# POV_02.net
KiCad netlist of a schematic drawn in EAGLE
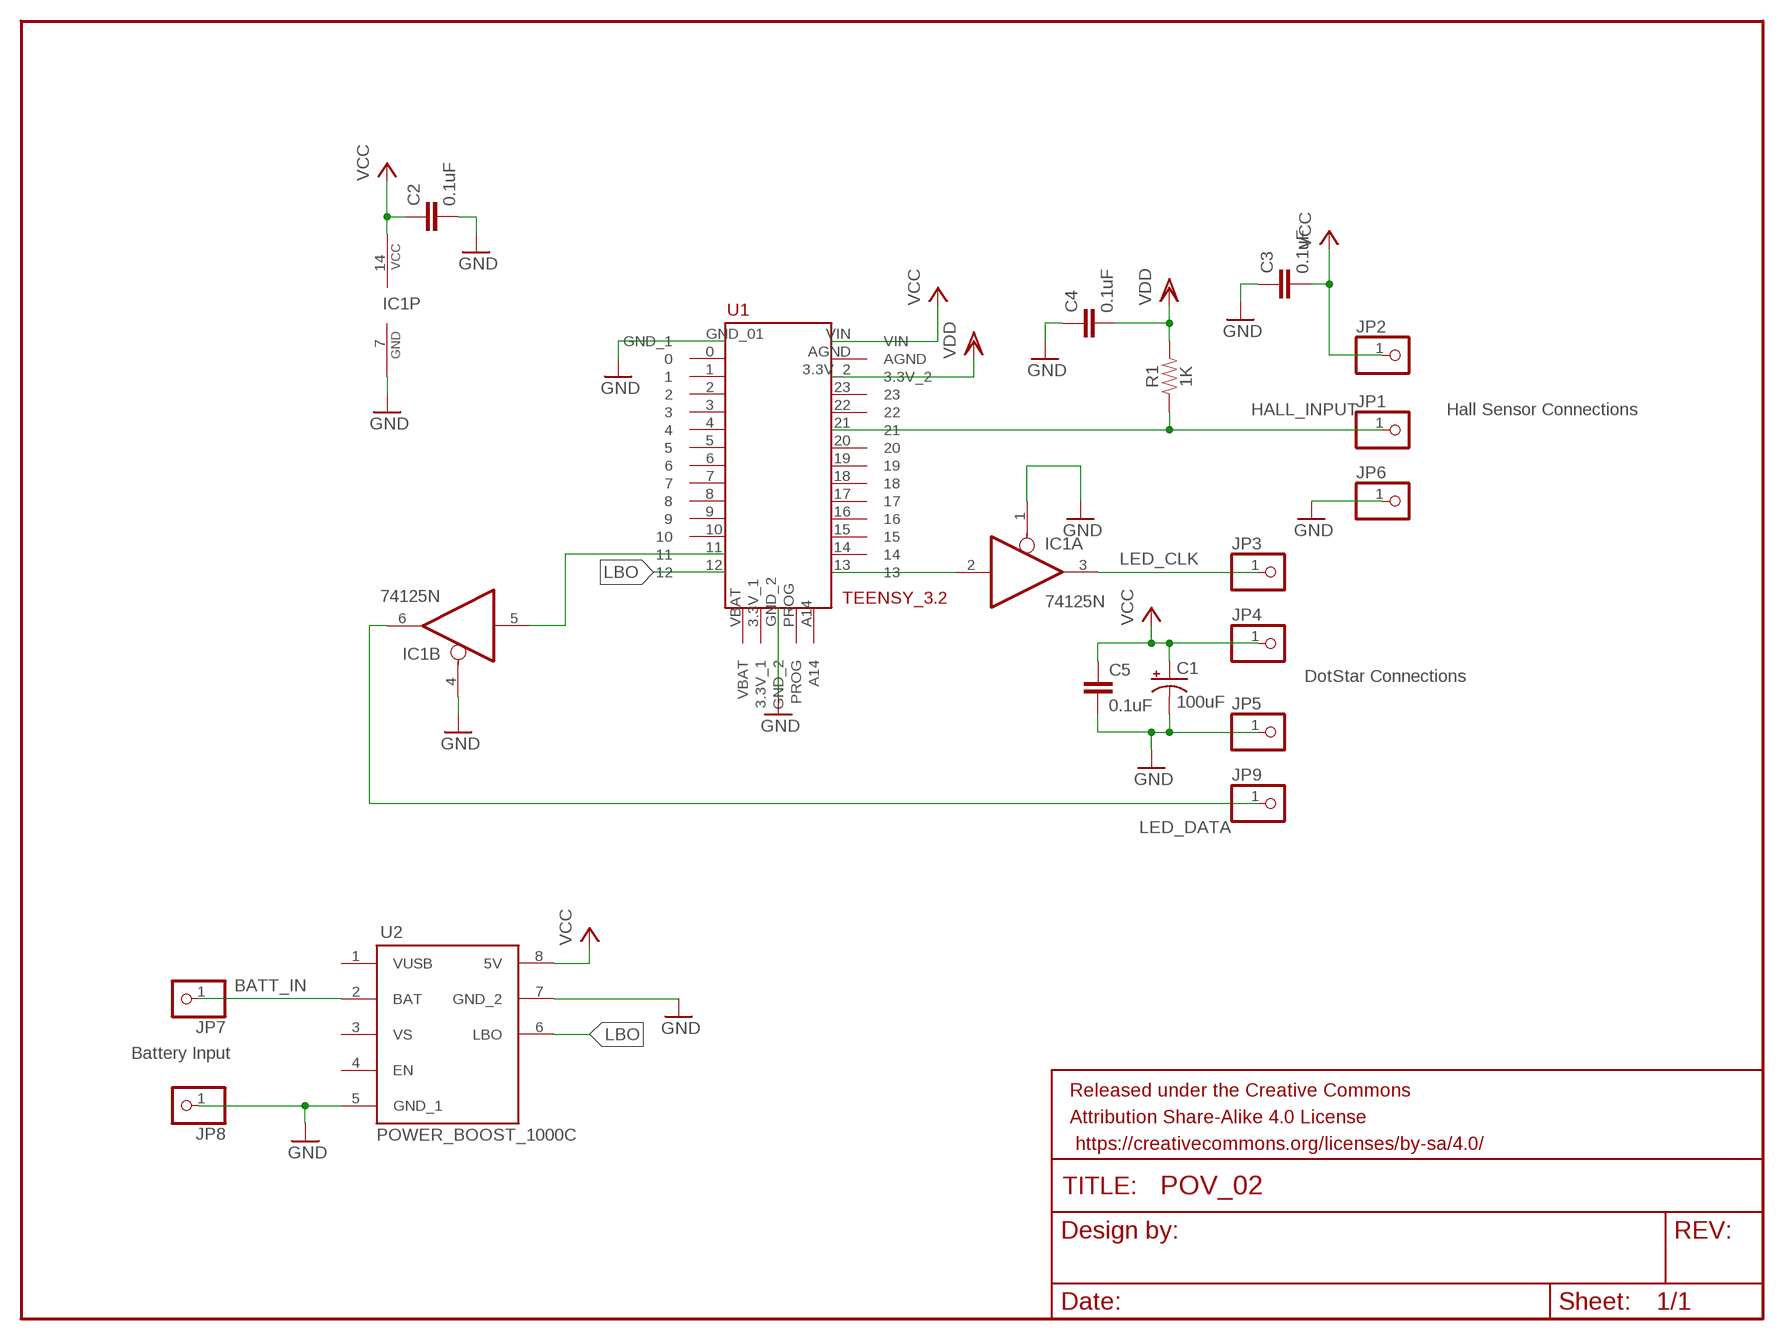
[diagram p0: schematic, sheet 1]

(export (version "E")
  (design (tool "Eeschema 10.0.6"))
  (components
    (comp (ref "C1")
      (value "100uF")
      (footprint "eagle-import:CPOL-RADIAL-2.5MM-6.5MM")
      (libsource (lib "eagle-import") (part "100UF-POLAR-RADIAL-2.5MM-25V-20%"))
    )
    (comp (ref "C2")
      (value "0.1uF")
      (footprint "eagle-import:CAP-PTH-SMALL-KIT")
      (libsource (lib "eagle-import") (part "0.1UF-KIT-EZ-50V-20%"))
    )
    (comp (ref "C3")
      (value "0.1uF")
      (footprint "eagle-import:CAP-PTH-SMALL-KIT")
      (libsource (lib "eagle-import") (part "0.1UF-KIT-EZ-50V-20%"))
    )
    (comp (ref "C4")
      (value "0.1uF")
      (footprint "eagle-import:CAP-PTH-SMALL-KIT")
      (libsource (lib "eagle-import") (part "0.1UF-KIT-EZ-50V-20%"))
    )
    (comp (ref "C5")
      (value "0.1uF")
      (footprint "eagle-import:CAP-PTH-SMALL-KIT")
      (libsource (lib "eagle-import") (part "0.1UF-KIT-EZ-50V-20%"))
    )
    (comp (ref "FRAME1")
      (value "FRAME-LETTERNO_PACKAGE")
      (footprint "eagle-import:DUMMY")
      (fields (field (name "DESIGNER") "Nobody"))
      (libsource (lib "eagle-import") (part "FRAME-LETTERNO_PACKAGE"))
    )
    (comp (ref "IC1")
      (value "74125N")
      (footprint "eagle-import:DIL14")
      (libsource (lib "eagle-import") (part "74125N"))
    )
    (comp (ref "JP1")
      (value "HEADER-1X1ROUND")
      (footprint "eagle-import:1X01_ROUND")
      (libsource (lib "eagle-import") (part "HEADER-1X1ROUND"))
    )
    (comp (ref "JP2")
      (value "HEADER-1X1ROUND")
      (footprint "eagle-import:1X01_ROUND")
      (libsource (lib "eagle-import") (part "HEADER-1X1ROUND"))
    )
    (comp (ref "JP3")
      (value "HEADER-1X1ROUND")
      (footprint "eagle-import:1X01_ROUND")
      (libsource (lib "eagle-import") (part "HEADER-1X1ROUND"))
    )
    (comp (ref "JP4")
      (value "HEADER-1X1ROUND")
      (footprint "eagle-import:1X01_ROUND")
      (libsource (lib "eagle-import") (part "HEADER-1X1ROUND"))
    )
    (comp (ref "JP5")
      (value "HEADER-1X1ROUND")
      (footprint "eagle-import:1X01_ROUND")
      (libsource (lib "eagle-import") (part "HEADER-1X1ROUND"))
    )
    (comp (ref "JP6")
      (value "HEADER-1X1ROUND")
      (footprint "eagle-import:1X01_ROUND")
      (libsource (lib "eagle-import") (part "HEADER-1X1ROUND"))
    )
    (comp (ref "JP7")
      (value "HEADER-1X1ROUND")
      (footprint "eagle-import:1X01_ROUND")
      (libsource (lib "eagle-import") (part "HEADER-1X1ROUND"))
    )
    (comp (ref "JP8")
      (value "HEADER-1X1ROUND")
      (footprint "eagle-import:1X01_ROUND")
      (libsource (lib "eagle-import") (part "HEADER-1X1ROUND"))
    )
    (comp (ref "JP9")
      (value "HEADER-1X1ROUND")
      (footprint "eagle-import:1X01_ROUND")
      (libsource (lib "eagle-import") (part "HEADER-1X1ROUND"))
    )
    (comp (ref "R1")
      (value "1K")
      (footprint "eagle-import:AXIAL-0.3")
      (libsource (lib "eagle-import") (part "RESISTORAXIAL-0.3"))
    )
    (comp (ref "U1")
      (value "TEENSY_3.2")
      (footprint "eagle-import:TEENSEY_3.2")
      (libsource (lib "eagle-import") (part "TEENSY_3.2"))
    )
    (comp (ref "U2")
      (value "POWER_BOOST_1000C")
      (footprint "eagle-import:POWER_BOOST_1000C")
      (libsource (lib "eagle-import") (part "POWER_BOOST_1000C"))
    )
  )
  (nets
    (net (code "1") (name "/BATT_IN") (class "Default")
      (node (ref "JP7") (pin "1") (pinfunction "1_1") (pintype "passive"))
      (node (ref "U2") (pin "2") (pinfunction "BAT_2") (pintype "bidirectional"))
    )
    (net (code "2") (name "/HALL_INPUT") (class "Default")
      (node (ref "JP1") (pin "1") (pinfunction "1_1") (pintype "passive"))
      (node (ref "R1") (pin "P$1") (pinfunction "1_P$1") (pintype "passive"))
      (node (ref "U1") (pin "21") (pinfunction "21_21") (pintype "bidirectional"))
    )
    (net (code "3") (name "/LED_CLK") (class "Default")
      (node (ref "IC1") (pin "3") (pinfunction "O_3") (pintype "tri_state"))
      (node (ref "JP3") (pin "1") (pinfunction "1_1") (pintype "passive"))
    )
    (net (code "4") (name "/LED_DATA") (class "Default")
      (node (ref "IC1") (pin "6") (pinfunction "O_6") (pintype "tri_state"))
      (node (ref "JP9") (pin "1") (pinfunction "1_1") (pintype "passive"))
    )
    (net (code "5") (name "GND") (class "Default")
      (node (ref "C1") (pin "2") (pinfunction "-_2") (pintype "passive"))
      (node (ref "C2") (pin "2") (pinfunction "2_2") (pintype "passive"))
      (node (ref "C3") (pin "1") (pinfunction "1_1") (pintype "passive"))
      (node (ref "C4") (pin "1") (pinfunction "1_1") (pintype "passive"))
      (node (ref "C5") (pin "2") (pinfunction "2_2") (pintype "passive"))
      (node (ref "IC1") (pin "1") (pinfunction "OE_1") (pintype "input"))
      (node (ref "IC1") (pin "4") (pinfunction "OE_4") (pintype "input"))
      (node (ref "IC1") (pin "7") (pinfunction "GND_7") (pintype "power_in"))
      (node (ref "JP5") (pin "1") (pinfunction "1_1") (pintype "passive"))
      (node (ref "JP6") (pin "1") (pinfunction "1_1") (pintype "passive"))
      (node (ref "JP8") (pin "1") (pinfunction "1_1") (pintype "passive"))
      (node (ref "U1") (pin "GND_01") (pinfunction "GND_1_GND_01") (pintype "bidirectional"))
      (node (ref "U1") (pin "GND_2") (pinfunction "GND_2_GND_2") (pintype "bidirectional"))
      (node (ref "U2") (pin "5") (pinfunction "GND_1_5") (pintype "bidirectional"))
      (node (ref "U2") (pin "7") (pinfunction "GND_2_7") (pintype "bidirectional"))
    )
    (net (code "6") (name "LBO") (class "Default")
      (node (ref "U1") (pin "12") (pinfunction "12_12") (pintype "bidirectional"))
      (node (ref "U2") (pin "6") (pinfunction "LBO_6") (pintype "bidirectional"))
    )
    (net (code "7") (name "Net-(IC1A-I)") (class "Default")
      (node (ref "IC1") (pin "2") (pinfunction "I_2") (pintype "input"))
      (node (ref "U1") (pin "13") (pinfunction "13_13") (pintype "bidirectional"))
    )
    (net (code "8") (name "Net-(IC1B-I)") (class "Default")
      (node (ref "IC1") (pin "5") (pinfunction "I_5") (pintype "input"))
      (node (ref "U1") (pin "11") (pinfunction "11_11") (pintype "bidirectional"))
    )
    (net (code "9") (name "VCC") (class "Default")
      (node (ref "C1") (pin "1") (pinfunction "+_1") (pintype "passive"))
      (node (ref "C2") (pin "1") (pinfunction "1_1") (pintype "passive"))
      (node (ref "C3") (pin "2") (pinfunction "2_2") (pintype "passive"))
      (node (ref "C5") (pin "1") (pinfunction "1_1") (pintype "passive"))
      (node (ref "IC1") (pin "14") (pinfunction "VCC_14") (pintype "power_in"))
      (node (ref "JP2") (pin "1") (pinfunction "1_1") (pintype "passive"))
      (node (ref "JP4") (pin "1") (pinfunction "1_1") (pintype "passive"))
      (node (ref "U1") (pin "VIN") (pinfunction "VIN_VIN") (pintype "bidirectional"))
      (node (ref "U2") (pin "8") (pinfunction "5V_8") (pintype "bidirectional"))
    )
    (net (code "10") (name "VDD") (class "Default")
      (node (ref "C4") (pin "2") (pinfunction "2_2") (pintype "passive"))
      (node (ref "R1") (pin "P$2") (pinfunction "2_P$2") (pintype "passive"))
      (node (ref "U1") (pin "3.3V_2") (pinfunction "3.3V_2_3.3V_2") (pintype "bidirectional"))
    )
    (net (code "11") (name "unconnected-(U1-Pad0)") (class "Default")
      (node (ref "U1") (pin "0") (pinfunction "0_0") (pintype "bidirectional"))
    )
    (net (code "12") (name "unconnected-(U1-Pad1)") (class "Default")
      (node (ref "U1") (pin "1") (pinfunction "1_1") (pintype "bidirectional"))
    )
    (net (code "13") (name "unconnected-(U1-Pad2)") (class "Default")
      (node (ref "U1") (pin "2") (pinfunction "2_2") (pintype "bidirectional"))
    )
    (net (code "14") (name "unconnected-(U1-Pad3)") (class "Default")
      (node (ref "U1") (pin "3") (pinfunction "3_3") (pintype "bidirectional"))
    )
    (net (code "15") (name "unconnected-(U1-Pad3.3V_1)") (class "Default")
      (node (ref "U1") (pin "3.3V_1") (pinfunction "3.3V_1_3.3V_1") (pintype "bidirectional"))
    )
    (net (code "16") (name "unconnected-(U1-Pad4)") (class "Default")
      (node (ref "U1") (pin "4") (pinfunction "4_4") (pintype "bidirectional"))
    )
    (net (code "17") (name "unconnected-(U1-Pad5)") (class "Default")
      (node (ref "U1") (pin "5") (pinfunction "5_5") (pintype "bidirectional"))
    )
    (net (code "18") (name "unconnected-(U1-Pad6)") (class "Default")
      (node (ref "U1") (pin "6") (pinfunction "6_6") (pintype "bidirectional"))
    )
    (net (code "19") (name "unconnected-(U1-Pad7)") (class "Default")
      (node (ref "U1") (pin "7") (pinfunction "7_7") (pintype "bidirectional"))
    )
    (net (code "20") (name "unconnected-(U1-Pad8)") (class "Default")
      (node (ref "U1") (pin "8") (pinfunction "8_8") (pintype "bidirectional"))
    )
    (net (code "21") (name "unconnected-(U1-Pad9)") (class "Default")
      (node (ref "U1") (pin "9") (pinfunction "9_9") (pintype "bidirectional"))
    )
    (net (code "22") (name "unconnected-(U1-Pad10)") (class "Default")
      (node (ref "U1") (pin "10") (pinfunction "10_10") (pintype "bidirectional"))
    )
    (net (code "23") (name "unconnected-(U1-Pad14)") (class "Default")
      (node (ref "U1") (pin "14") (pinfunction "14_14") (pintype "bidirectional"))
    )
    (net (code "24") (name "unconnected-(U1-Pad15)") (class "Default")
      (node (ref "U1") (pin "15") (pinfunction "15_15") (pintype "bidirectional"))
    )
    (net (code "25") (name "unconnected-(U1-Pad16)") (class "Default")
      (node (ref "U1") (pin "16") (pinfunction "16_16") (pintype "bidirectional"))
    )
    (net (code "26") (name "unconnected-(U1-Pad17)") (class "Default")
      (node (ref "U1") (pin "17") (pinfunction "17_17") (pintype "bidirectional"))
    )
    (net (code "27") (name "unconnected-(U1-Pad18)") (class "Default")
      (node (ref "U1") (pin "18") (pinfunction "18_18") (pintype "bidirectional"))
    )
    (net (code "28") (name "unconnected-(U1-Pad19)") (class "Default")
      (node (ref "U1") (pin "19") (pinfunction "19_19") (pintype "bidirectional"))
    )
    (net (code "29") (name "unconnected-(U1-Pad20)") (class "Default")
      (node (ref "U1") (pin "20") (pinfunction "20_20") (pintype "bidirectional"))
    )
    (net (code "30") (name "unconnected-(U1-Pad22)") (class "Default")
      (node (ref "U1") (pin "22") (pinfunction "22_22") (pintype "bidirectional"))
    )
    (net (code "31") (name "unconnected-(U1-Pad23)") (class "Default")
      (node (ref "U1") (pin "23") (pinfunction "23_23") (pintype "bidirectional"))
    )
    (net (code "32") (name "unconnected-(U1-PadA14)") (class "Default")
      (node (ref "U1") (pin "A14") (pinfunction "A14_A14") (pintype "bidirectional"))
    )
    (net (code "33") (name "unconnected-(U1-PadAGND)") (class "Default")
      (node (ref "U1") (pin "AGND") (pinfunction "AGND_AGND") (pintype "bidirectional"))
    )
    (net (code "34") (name "unconnected-(U1-PadPROG)") (class "Default")
      (node (ref "U1") (pin "PROG") (pinfunction "PROG_PROG") (pintype "bidirectional"))
    )
    (net (code "35") (name "unconnected-(U1-PadVBAT)") (class "Default")
      (node (ref "U1") (pin "VBAT") (pinfunction "VBAT_VBAT") (pintype "bidirectional"))
    )
    (net (code "36") (name "unconnected-(U2-EN-Pad4)") (class "Default")
      (node (ref "U2") (pin "4") (pinfunction "EN_4") (pintype "bidirectional"))
    )
    (net (code "37") (name "unconnected-(U2-VS-Pad3)") (class "Default")
      (node (ref "U2") (pin "3") (pinfunction "VS_3") (pintype "bidirectional"))
    )
    (net (code "38") (name "unconnected-(U2-VUSB-Pad1)") (class "Default")
      (node (ref "U2") (pin "1") (pinfunction "VUSB_1") (pintype "bidirectional"))
    )
  )
)
